# 6coils-1-discrete.net
KiCad netlist of a schematic drawn in EasyEDA
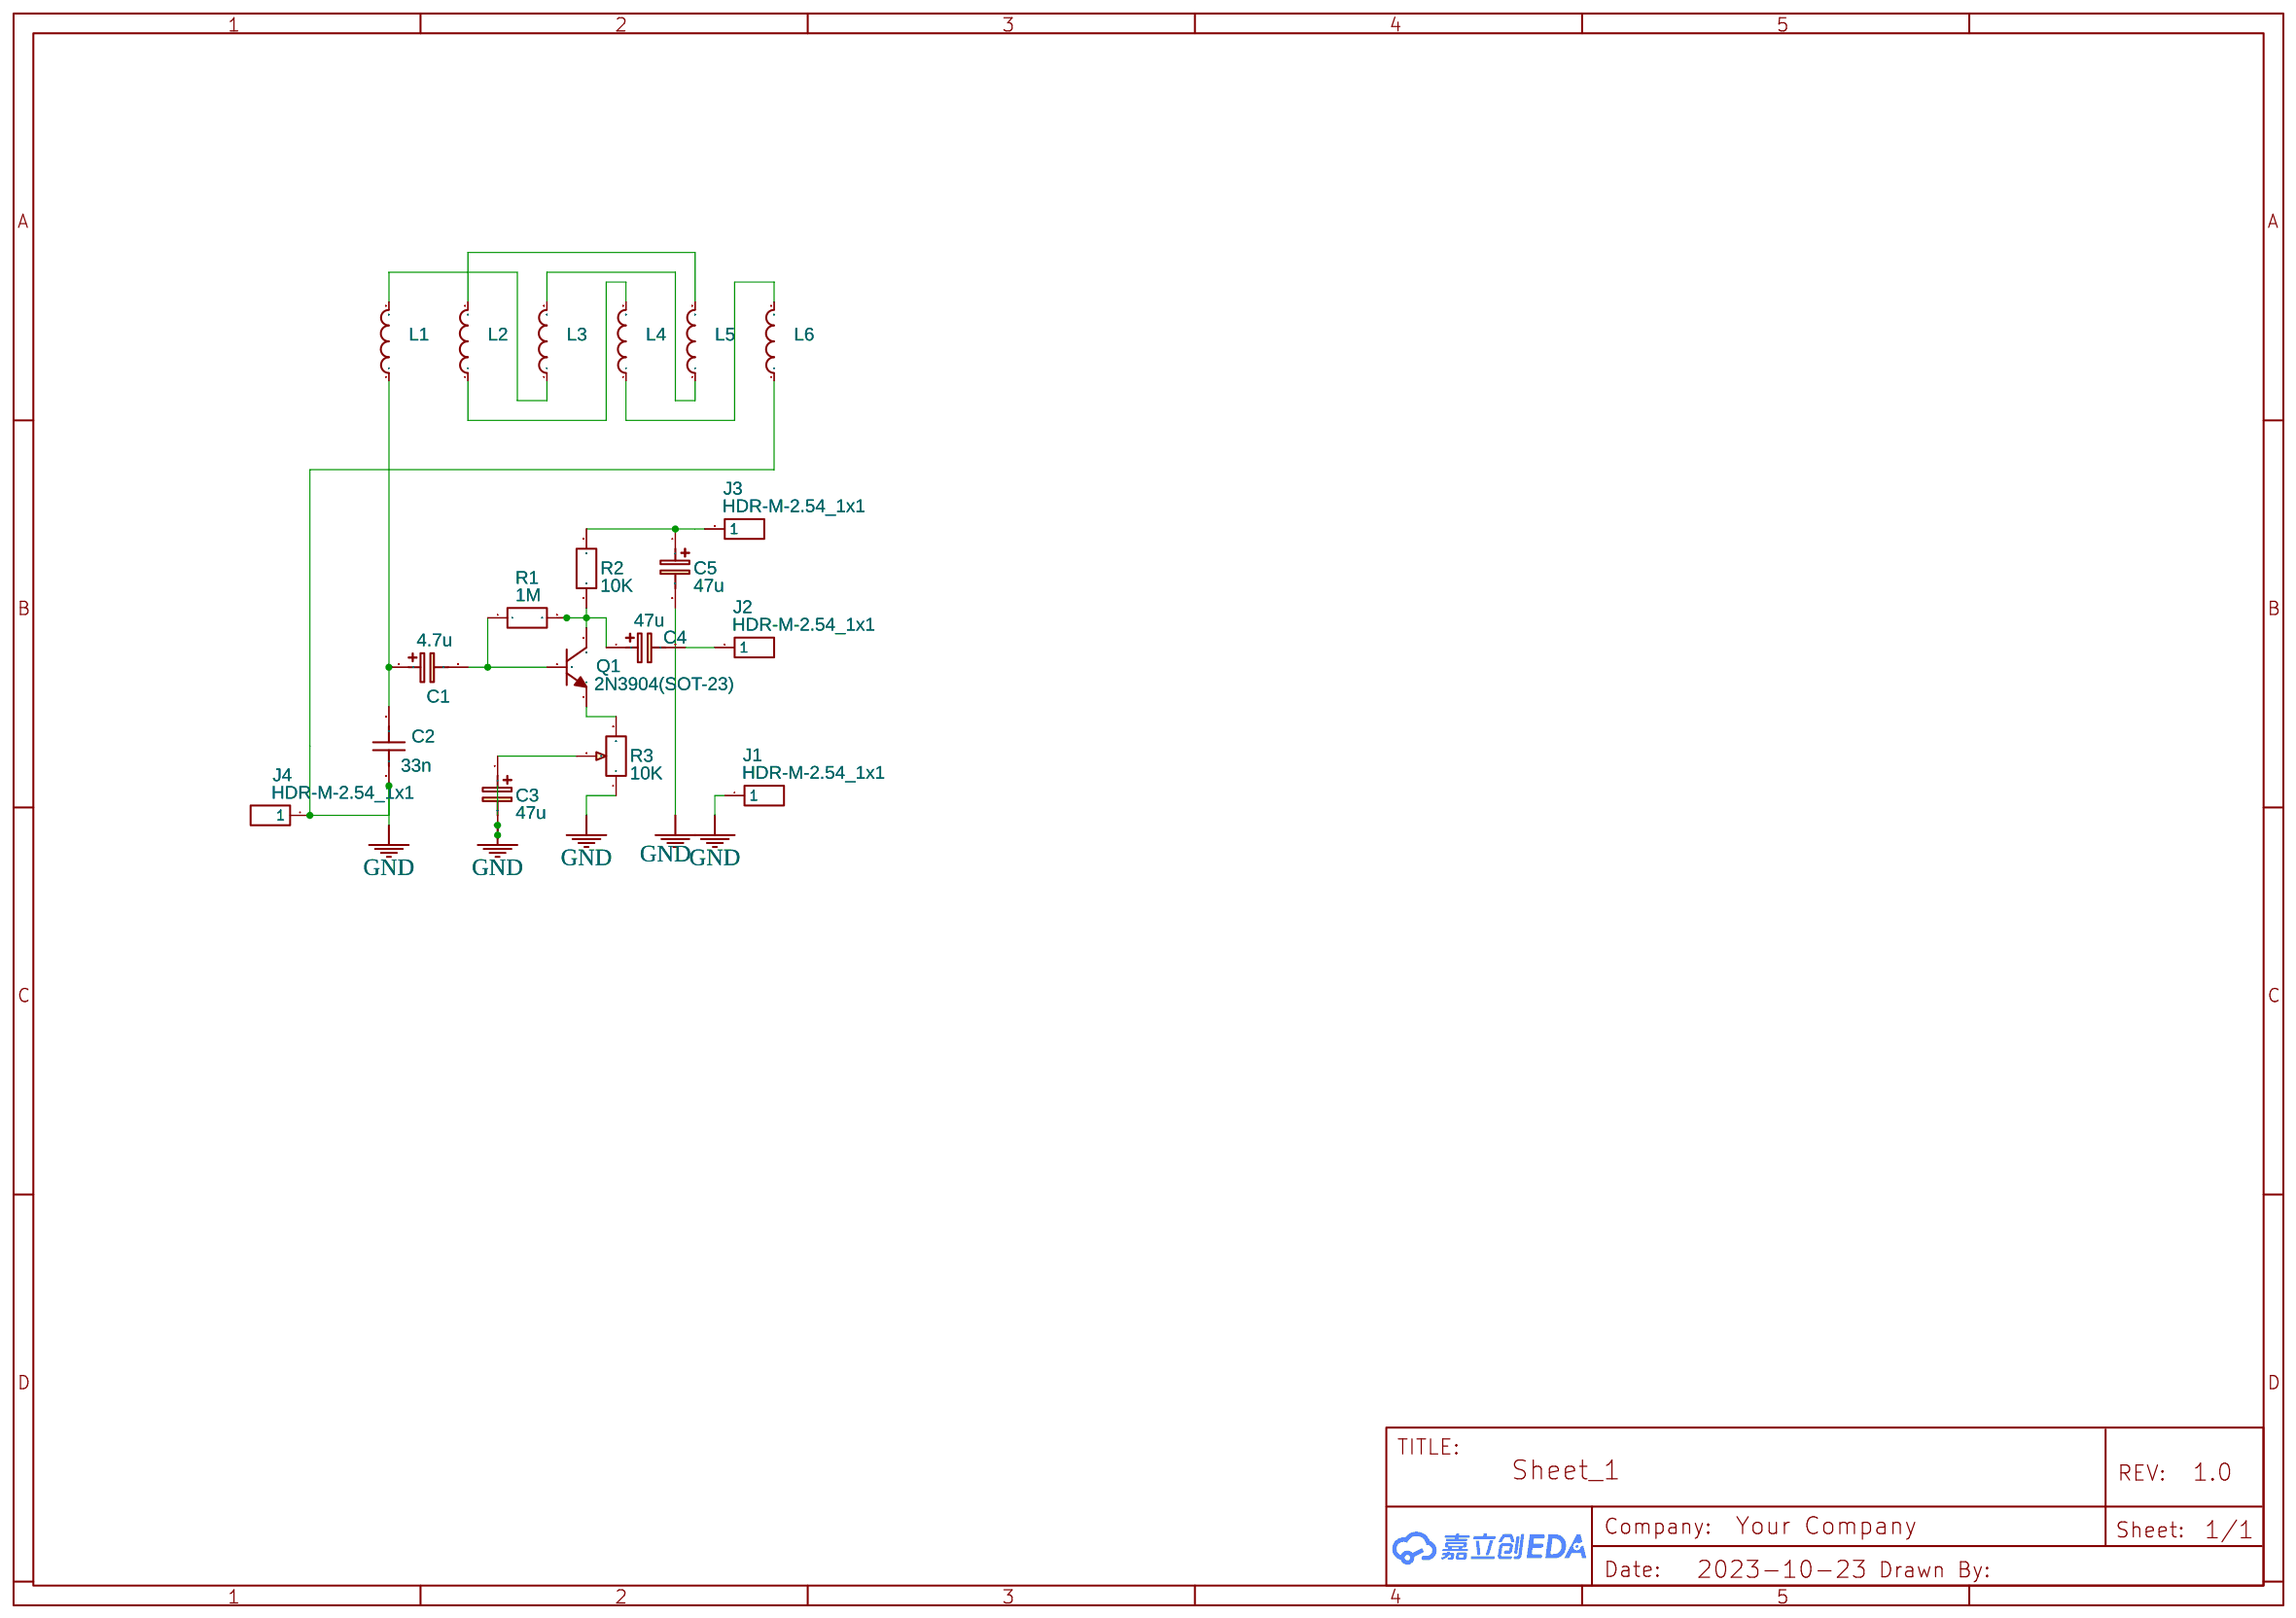
[diagram p0: schematic sheet]

(export (version "E")
  (design (tool "Eeschema 10.0.6"))
  (components
    (comp (ref "C1") (value "4.7u") (libsource (lib "") (part "C_Tan_SMD_A_EU_1")))
    (comp (ref "C2") (value "33n") (libsource (lib "") (part "C_0603_US")))
    (comp (ref "C3") (value "47u") (libsource (lib "") (part "C_Tan_SMD_A_EU")))
    (comp (ref "C4") (value "47u") (libsource (lib "") (part "C_Tan_SMD_A_EU_2")))
    (comp (ref "C5") (value "47u") (libsource (lib "") (part "C_Tan_SMD_A_EU_3")))
    (comp (ref "J1")
      (value "HDR-M-2.54_1x1")
      (fields (field (name "BOM_Supplier Part") "C81276"))
      (libsource (lib "") (part "HDR-M-2.54_1x1"))
    )
    (comp (ref "J2")
      (value "HDR-M-2.54_1x1")
      (fields (field (name "BOM_Supplier Part") "C81276"))
      (libsource (lib "") (part "HDR-M-2.54_1x1"))
    )
    (comp (ref "J3")
      (value "HDR-M-2.54_1x1")
      (fields (field (name "BOM_Supplier Part") "C81276"))
      (libsource (lib "") (part "HDR-M-2.54_1x1"))
    )
    (comp (ref "J4")
      (value "HDR-M-2.54_1x1")
      (fields (field (name "BOM_Supplier Part") "C81276"))
      (libsource (lib "") (part "HDR-M-2.54_1x1_1"))
    )
    (comp (ref "L1")
      (value "INDUCTOR_SMD:L_COILCRAFT_XXL4040")
      (fields (field (name "Manufacturer Part") "Inductor_SMD:L_Coilcraft_XxL4040"))
      (libsource (lib "") (part "INDUCTOR_SMD{colon}L_COILCRAFT_XXL4040_1"))
    )
    (comp (ref "L2")
      (value "INDUCTOR_SMD:L_COILCRAFT_XXL4040")
      (fields (field (name "Manufacturer Part") "Inductor_SMD:L_Coilcraft_XxL4040"))
      (libsource (lib "") (part "INDUCTOR_SMD{colon}L_COILCRAFT_XXL4040_1"))
    )
    (comp (ref "L3")
      (value "INDUCTOR_SMD:L_COILCRAFT_XXL4040")
      (fields (field (name "Manufacturer Part") "Inductor_SMD:L_Coilcraft_XxL4040"))
      (libsource (lib "") (part "INDUCTOR_SMD{colon}L_COILCRAFT_XXL4040"))
    )
    (comp (ref "L4")
      (value "INDUCTOR_SMD:L_COILCRAFT_XXL4040")
      (fields (field (name "Manufacturer Part") "Inductor_SMD:L_Coilcraft_XxL4040"))
      (libsource (lib "") (part "INDUCTOR_SMD{colon}L_COILCRAFT_XXL4040"))
    )
    (comp (ref "L5")
      (value "INDUCTOR_SMD:L_COILCRAFT_XXL4040")
      (fields (field (name "Manufacturer Part") "Inductor_SMD:L_Coilcraft_XxL4040"))
      (libsource (lib "") (part "INDUCTOR_SMD{colon}L_COILCRAFT_XXL4040"))
    )
    (comp (ref "L6")
      (value "INDUCTOR_SMD:L_COILCRAFT_XXL4040")
      (fields (field (name "Manufacturer Part") "Inductor_SMD:L_Coilcraft_XxL4040"))
      (libsource (lib "") (part "INDUCTOR_SMD{colon}L_COILCRAFT_XXL4040"))
    )
    (comp (ref "Q1")
      (value "2N3904(SOT-23)")
      (fields
        (field (name "BOM_Manufacturer Part") "2n3904S-RTK/PS")
        (field (name "BOM_Supplier Part") "C18536")
      )
      (libsource (lib "") (part "2N3904(SOT-23)"))
    )
    (comp (ref "R1") (value "1M") (libsource (lib "") (part "R_0603_EU")))
    (comp (ref "R2") (value "10K") (libsource (lib "") (part "R_0603_EU_1")))
    (comp (ref "R3")
      (value "10K")
      (fields (field (name "Manufacturer Part") "RM063-103 10K") (field (name "Manufacturer") "JML"))
      (libsource (lib "") (part "RM063-103 10K"))
    )
  )
  (nets
    (net (code "1") (name "GND") (class "Default")
      (node (ref "C2") (pin "1") (pinfunction "1_1") (pintype "unspecified"))
      (node (ref "C3") (pin "2") (pinfunction "2_2") (pintype "unspecified"))
      (node (ref "C5") (pin "2") (pinfunction "2_2") (pintype "unspecified"))
      (node (ref "J1") (pin "1") (pinfunction "1_1") (pintype "input"))
      (node (ref "J4") (pin "1") (pinfunction "1_1") (pintype "input"))
      (node (ref "L6") (pin "1") (pinfunction "1_1") (pintype "unspecified"))
      (node (ref "R3") (pin "1") (pinfunction "1_1") (pintype "input"))
    )
    (net (code "2") (name "Net-(C1-Pad1)") (class "Default")
      (node (ref "C1") (pin "1") (pinfunction "1_1") (pintype "unspecified"))
      (node (ref "C2") (pin "2") (pinfunction "2_2") (pintype "unspecified"))
      (node (ref "L1") (pin "1") (pinfunction "1_1") (pintype "unspecified"))
    )
    (net (code "3") (name "Net-(C3-Pad1)") (class "Default")
      (node (ref "C3") (pin "1") (pinfunction "1_1") (pintype "unspecified"))
      (node (ref "R3") (pin "2") (pinfunction "2_2") (pintype "input"))
    )
    (net (code "4") (name "Net-(C4-Pad2)") (class "Default")
      (node (ref "C4") (pin "2") (pinfunction "2_2") (pintype "unspecified"))
      (node (ref "J2") (pin "1") (pinfunction "1_1") (pintype "input"))
    )
    (net (code "5") (name "Net-(C5-Pad1)") (class "Default")
      (node (ref "C5") (pin "1") (pinfunction "1_1") (pintype "unspecified"))
      (node (ref "J3") (pin "1") (pinfunction "1_1") (pintype "input"))
      (node (ref "R2") (pin "2") (pinfunction "2_2") (pintype "unspecified"))
    )
    (net (code "6") (name "Net-(L1-Pad2)") (class "Default")
      (node (ref "L1") (pin "2") (pinfunction "2_2") (pintype "unspecified"))
      (node (ref "L3") (pin "1") (pinfunction "1_1") (pintype "unspecified"))
    )
    (net (code "7") (name "Net-(L2-Pad1)") (class "Default")
      (node (ref "L2") (pin "1") (pinfunction "1_1") (pintype "unspecified"))
      (node (ref "L4") (pin "2") (pinfunction "2_2") (pintype "unspecified"))
    )
    (net (code "8") (name "Net-(L2-Pad2)") (class "Default")
      (node (ref "L2") (pin "2") (pinfunction "2_2") (pintype "unspecified"))
      (node (ref "L5") (pin "2") (pinfunction "2_2") (pintype "unspecified"))
    )
    (net (code "9") (name "Net-(L3-Pad2)") (class "Default")
      (node (ref "L3") (pin "2") (pinfunction "2_2") (pintype "unspecified"))
      (node (ref "L5") (pin "1") (pinfunction "1_1") (pintype "unspecified"))
    )
    (net (code "10") (name "Net-(L4-Pad1)") (class "Default")
      (node (ref "L4") (pin "1") (pinfunction "1_1") (pintype "unspecified"))
      (node (ref "L6") (pin "2") (pinfunction "2_2") (pintype "unspecified"))
    )
    (net (code "11") (name "Net-(Q1-B)") (class "Default")
      (node (ref "C1") (pin "2") (pinfunction "2_2") (pintype "unspecified"))
      (node (ref "Q1") (pin "2") (pinfunction "B_2") (pintype "input"))
      (node (ref "R1") (pin "1") (pinfunction "1_1") (pintype "unspecified"))
    )
    (net (code "12") (name "Net-(Q1-C)") (class "Default")
      (node (ref "C4") (pin "1") (pinfunction "1_1") (pintype "unspecified"))
      (node (ref "Q1") (pin "3") (pinfunction "C_3") (pintype "input"))
      (node (ref "R1") (pin "2") (pinfunction "2_2") (pintype "unspecified"))
      (node (ref "R2") (pin "1") (pinfunction "1_1") (pintype "unspecified"))
    )
    (net (code "13") (name "Net-(Q1-E)") (class "Default")
      (node (ref "Q1") (pin "1") (pinfunction "E_1") (pintype "input"))
      (node (ref "R3") (pin "3") (pinfunction "3_3") (pintype "input"))
    )
  )
)
